# EEM_connector_Wenzel.net
KiCad netlist of a schematic drawn in Altium Designer
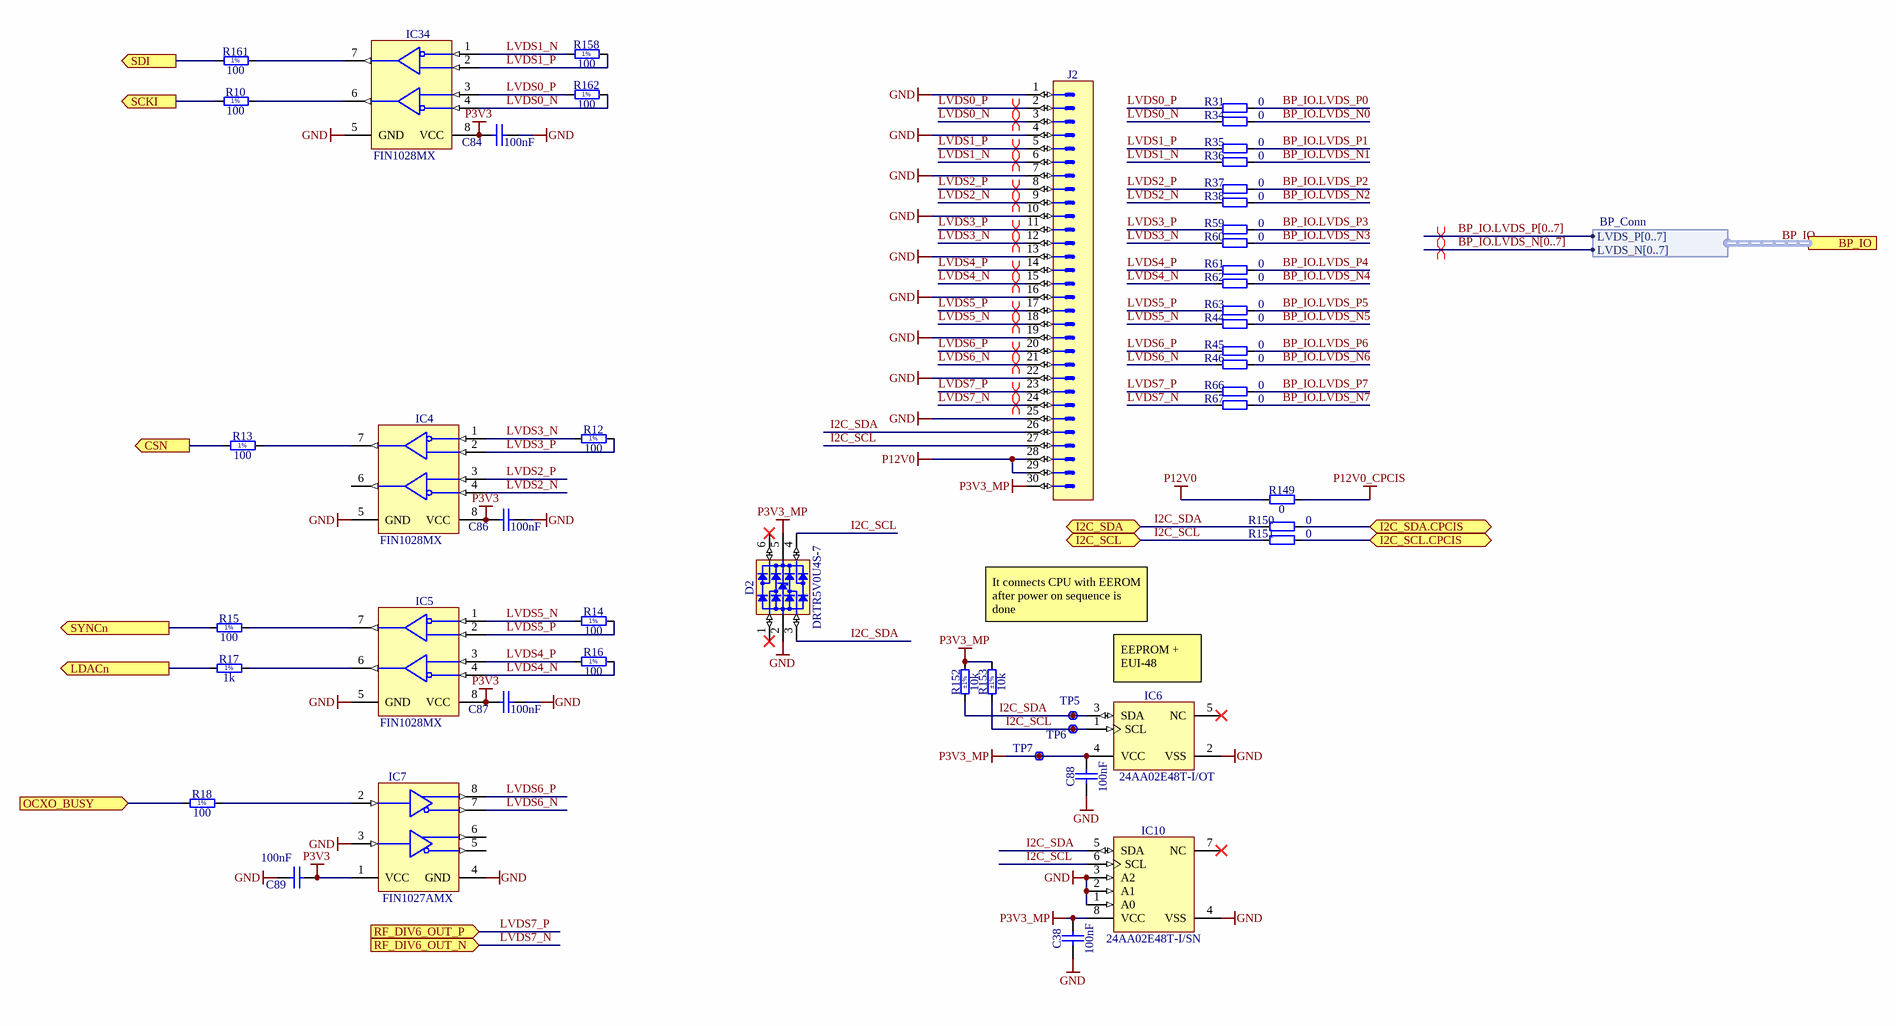
[diagram p0: EEM_connector_Wenzel.SchDoc]

(export (version "E")
  (design (tool "Eeschema 10.0.6"))
  (components
    (comp (ref "C38")
      (value "100nF")
      (footprint "CAPC1005X55N")
      (description "Non-polarised capacitor")
      (fields
        (field (name "PART NUMBER") "CC0402_100NF_16V_10%_X5R")
        (field (name "VOLTAGE") "16V")
        (field (name "AUTHOR") "CERN DEM JLC")
      )
      (libsource (lib "Capacitors") (part "Capacitor - non polarized"))
    )
    (comp (ref "C84")
      (value "100nF")
      (footprint "CAPC1005X55N")
      (description "Non-polarised capacitor")
      (fields
        (field (name "PART NUMBER") "CC0402_100NF_16V_10%_X5R")
        (field (name "VOLTAGE") "16V")
        (field (name "AUTHOR") "CERN DEM JLC")
      )
      (libsource (lib "Capacitors") (part "Capacitor - non polarized"))
    )
    (comp (ref "C86")
      (value "100nF")
      (footprint "CAPC1005X55N")
      (description "Non-polarised capacitor")
      (fields
        (field (name "PART NUMBER") "CC0402_100NF_16V_10%_X5R")
        (field (name "VOLTAGE") "16V")
        (field (name "AUTHOR") "CERN DEM JLC")
      )
      (libsource (lib "Capacitors") (part "Capacitor - non polarized"))
    )
    (comp (ref "C87")
      (value "100nF")
      (footprint "CAPC1005X55N")
      (description "Non-polarised capacitor")
      (fields
        (field (name "PART NUMBER") "CC0402_100NF_16V_10%_X5R")
        (field (name "VOLTAGE") "16V")
        (field (name "AUTHOR") "CERN DEM JLC")
      )
      (libsource (lib "Capacitors") (part "Capacitor - non polarized"))
    )
    (comp (ref "C88")
      (value "100nF")
      (footprint "CAPC1005X55N")
      (description "Non-polarised capacitor")
      (fields
        (field (name "PART NUMBER") "CC0402_100NF_16V_10%_X5R")
        (field (name "VOLTAGE") "16V")
        (field (name "AUTHOR") "CERN DEM JLC")
      )
      (libsource (lib "Capacitors") (part "Capacitor - non polarized"))
    )
    (comp (ref "C89")
      (value "100nF")
      (footprint "CAPC1005X55N")
      (description "Non-polarised capacitor")
      (fields
        (field (name "PART NUMBER") "CC0402_100NF_16V_10%_X5R")
        (field (name "VOLTAGE") "16V")
        (field (name "AUTHOR") "CERN DEM JLC")
      )
      (libsource (lib "Capacitors") (part "Capacitor - non polarized"))
    )
    (comp (ref "D2")
      (value "DRTR5V0U4S-7")
      (footprint "SOT65P210X110-6N")
      (description "Integrated Quad Ultra-Low Capacitance ESD Protection")
      (fields (field (name "MANUFACTURER") "DIODES") (field (name "AUTHOR") "GK"))
      (libsource (lib "Diodes") (part "D_TVS_DRTR5V0U4S-7"))
    )
    (comp (ref "IC4")
      (value "FIN1028MX")
      (footprint "SOIC127P600X175-8N")
      (description "3.3V LVDS 2-Bit High-Speed Differential Reciever")
      (fields (field (name "MANUFACTURER") "ON Semiconductor") (field (name "AUTHOR") "GK"))
      (libsource (lib "LIBRARY_SCH") (part "IFC_FIN1028"))
    )
    (comp (ref "IC5")
      (value "FIN1028MX")
      (footprint "SOIC127P600X175-8N")
      (description "3.3V LVDS 2-Bit High-Speed Differential Reciever")
      (fields (field (name "MANUFACTURER") "ON Semiconductor") (field (name "AUTHOR") "GK"))
      (libsource (lib "LIBRARY_SCH") (part "IFC_FIN1028"))
    )
    (comp (ref "IC6")
      (value "24AA02E48T-I/OT")
      (footprint "SOT95P280X145-5N")
      (description "1.7V-5.5V, 2K I2C Serial EEPROM With EUI-48 Node Identity")
      (fields (field (name "MANUFACTURER") "MICROCHIP TECHNOLOGY") (field (name "AUTHOR") "CERN DEM MR"))
      (libsource (lib "ICs And Semiconductors") (part "24AA02E48T-I/OT"))
    )
    (comp (ref "IC7")
      (value "FIN1027AMX")
      (footprint "SOIC127P600X175-8N")
      (description "3.3V LVDS, 2-Bit, High-Speed, Differential Driver")
      (fields (field (name "MANUFACTURER") "ON Semiconductor") (field (name "AUTHOR") "GK"))
      (libsource (lib "LIBRARY_SCH") (part "IFC_FIN1027A"))
    )
    (comp (ref "IC10")
      (value "24AA02E48T-I/SN")
      (footprint "SOIC127P600X175-8N")
      (description "1.7V-5.5V, 2K I2C™ Serial EEPROMs with EUI-48™ Node Identity")
      (fields (field (name "MANUFACTURER") "MICROCHIP TECHNOLOGY") (field (name "AUTHOR") "CERN DEM MR"))
      (libsource (lib "ICs And Semiconductors") (part "24AA025E48-I/SN"))
    )
    (comp (ref "IC34")
      (value "FIN1028MX")
      (footprint "SOIC127P600X175-8N")
      (description "3.3V LVDS 2-Bit High-Speed Differential Reciever")
      (fields (field (name "MANUFACTURER") "ON Semiconductor") (field (name "AUTHOR") "GK"))
      (libsource (lib "LIBRARY_SCH") (part "IFC_FIN1028"))
    )
    (comp (ref "J2")
      (value "IDC")
      (footprint "3M_N2530-6002RB")
      (description "Connector 30 Male")
      (fields
        (field (name "PART NUMBER") "3M_N2530-6002RB")
        (field (name "MANUFACTURER") "3M")
        (field (name "AUTHOR") "CERN DEM JLC")
      )
      (libsource (lib "Connectors") (part "Connector 30 Male"))
    )
    (comp (ref "R10")
      (value "100")
      (footprint "RESC1005X40N")
      (description "Resistor - 1%")
      (fields
        (field (name "PART NUMBER") "R0402_100R_1%_0.0625W_100PPM")
        (field (name "POWER") "0.0625W")
        (field (name "AUTHOR") "CERN DEM JLC")
      )
      (libsource (lib "Resistors") (part "Resistor - 1%"))
    )
    (comp (ref "R12")
      (value "100")
      (footprint "RESC1005X40N")
      (description "Resistor - 1%")
      (fields
        (field (name "PART NUMBER") "R0402_100R_1%_0.0625W_100PPM")
        (field (name "POWER") "0.0625W")
        (field (name "AUTHOR") "CERN DEM JLC")
      )
      (libsource (lib "Resistors") (part "Resistor - 1%"))
    )
    (comp (ref "R13")
      (value "100")
      (footprint "RESC1005X40N")
      (description "Resistor - 1%")
      (fields
        (field (name "PART NUMBER") "R0402_100R_1%_0.0625W_100PPM")
        (field (name "POWER") "0.0625W")
        (field (name "AUTHOR") "CERN DEM JLC")
      )
      (libsource (lib "Resistors") (part "Resistor - 1%"))
    )
    (comp (ref "R14")
      (value "100")
      (footprint "RESC1005X40N")
      (description "Resistor - 1%")
      (fields
        (field (name "PART NUMBER") "R0402_100R_1%_0.0625W_100PPM")
        (field (name "POWER") "0.0625W")
        (field (name "AUTHOR") "CERN DEM JLC")
      )
      (libsource (lib "Resistors") (part "Resistor - 1%"))
    )
    (comp (ref "R15")
      (value "100")
      (footprint "RESC1005X40N")
      (description "Resistor - 1%")
      (fields
        (field (name "PART NUMBER") "R0402_100R_1%_0.0625W_100PPM")
        (field (name "POWER") "0.0625W")
        (field (name "AUTHOR") "CERN DEM JLC")
      )
      (libsource (lib "Resistors") (part "Resistor - 1%"))
    )
    (comp (ref "R16")
      (value "100")
      (footprint "RESC1005X40N")
      (description "Resistor - 1%")
      (fields
        (field (name "PART NUMBER") "R0402_100R_1%_0.0625W_100PPM")
        (field (name "POWER") "0.0625W")
        (field (name "AUTHOR") "CERN DEM JLC")
      )
      (libsource (lib "Resistors") (part "Resistor - 1%"))
    )
    (comp (ref "R17")
      (value "1k")
      (footprint "RESC1005X40N")
      (description "Resistor - 1%")
      (fields
        (field (name "PART NUMBER") "R0402_1K_1%_0.0625W_100PPM")
        (field (name "POWER") "0.0625W")
        (field (name "AUTHOR") "CERN DEM JLC")
      )
      (libsource (lib "Resistors") (part "Resistor - 1%"))
    )
    (comp (ref "R18")
      (value "100")
      (footprint "RESC1005X40N")
      (description "Resistor - 1%")
      (fields
        (field (name "PART NUMBER") "R0402_100R_1%_0.0625W_100PPM")
        (field (name "POWER") "0.0625W")
        (field (name "AUTHOR") "CERN DEM JLC")
      )
      (libsource (lib "Resistors") (part "Resistor - 1%"))
    )
    (comp (ref "R31")
      (value "0")
      (footprint "RESC1005X40N")
      (description "Resistor")
      (fields
        (field (name "PART NUMBER") "R0402_0R_JUMPER")
        (field (name "MANUFACTURER") "GENERIC")
        (field (name "AUTHOR") "CERN DEM JLC")
      )
      (libsource (lib "Resistors") (part "Resistor"))
    )
    (comp (ref "R34")
      (value "0")
      (footprint "RESC1005X40N")
      (description "Resistor")
      (fields
        (field (name "PART NUMBER") "R0402_0R_JUMPER")
        (field (name "MANUFACTURER") "GENERIC")
        (field (name "AUTHOR") "CERN DEM JLC")
      )
      (libsource (lib "Resistors") (part "Resistor"))
    )
    (comp (ref "R35")
      (value "0")
      (footprint "RESC1005X40N")
      (description "Resistor")
      (fields
        (field (name "PART NUMBER") "R0402_0R_JUMPER")
        (field (name "MANUFACTURER") "GENERIC")
        (field (name "AUTHOR") "CERN DEM JLC")
      )
      (libsource (lib "Resistors") (part "Resistor"))
    )
    (comp (ref "R36")
      (value "0")
      (footprint "RESC1005X40N")
      (description "Resistor")
      (fields
        (field (name "PART NUMBER") "R0402_0R_JUMPER")
        (field (name "MANUFACTURER") "GENERIC")
        (field (name "AUTHOR") "CERN DEM JLC")
      )
      (libsource (lib "Resistors") (part "Resistor"))
    )
    (comp (ref "R37")
      (value "0")
      (footprint "RESC1005X40N")
      (description "Resistor")
      (fields
        (field (name "PART NUMBER") "R0402_0R_JUMPER")
        (field (name "MANUFACTURER") "GENERIC")
        (field (name "AUTHOR") "CERN DEM JLC")
      )
      (libsource (lib "Resistors") (part "Resistor"))
    )
    (comp (ref "R38")
      (value "0")
      (footprint "RESC1005X40N")
      (description "Resistor")
      (fields
        (field (name "PART NUMBER") "R0402_0R_JUMPER")
        (field (name "MANUFACTURER") "GENERIC")
        (field (name "AUTHOR") "CERN DEM JLC")
      )
      (libsource (lib "Resistors") (part "Resistor"))
    )
    (comp (ref "R44")
      (value "0")
      (footprint "RESC1005X40N")
      (description "Resistor")
      (fields
        (field (name "PART NUMBER") "R0402_0R_JUMPER")
        (field (name "MANUFACTURER") "GENERIC")
        (field (name "AUTHOR") "CERN DEM JLC")
      )
      (libsource (lib "Resistors") (part "Resistor"))
    )
    (comp (ref "R45")
      (value "0")
      (footprint "RESC1005X40N")
      (description "Resistor")
      (fields
        (field (name "PART NUMBER") "R0402_0R_JUMPER")
        (field (name "MANUFACTURER") "GENERIC")
        (field (name "AUTHOR") "CERN DEM JLC")
      )
      (libsource (lib "Resistors") (part "Resistor"))
    )
    (comp (ref "R46")
      (value "0")
      (footprint "RESC1005X40N")
      (description "Resistor")
      (fields
        (field (name "PART NUMBER") "R0402_0R_JUMPER")
        (field (name "MANUFACTURER") "GENERIC")
        (field (name "AUTHOR") "CERN DEM JLC")
      )
      (libsource (lib "Resistors") (part "Resistor"))
    )
    (comp (ref "R59")
      (value "0")
      (footprint "RESC1005X40N")
      (description "Resistor")
      (fields
        (field (name "PART NUMBER") "R0402_0R_JUMPER")
        (field (name "MANUFACTURER") "GENERIC")
        (field (name "AUTHOR") "CERN DEM JLC")
      )
      (libsource (lib "Resistors") (part "Resistor"))
    )
    (comp (ref "R60")
      (value "0")
      (footprint "RESC1005X40N")
      (description "Resistor")
      (fields
        (field (name "PART NUMBER") "R0402_0R_JUMPER")
        (field (name "MANUFACTURER") "GENERIC")
        (field (name "AUTHOR") "CERN DEM JLC")
      )
      (libsource (lib "Resistors") (part "Resistor"))
    )
    (comp (ref "R61")
      (value "0")
      (footprint "RESC1005X40N")
      (description "Resistor")
      (fields
        (field (name "PART NUMBER") "R0402_0R_JUMPER")
        (field (name "MANUFACTURER") "GENERIC")
        (field (name "AUTHOR") "CERN DEM JLC")
      )
      (libsource (lib "Resistors") (part "Resistor"))
    )
    (comp (ref "R62")
      (value "0")
      (footprint "RESC1005X40N")
      (description "Resistor")
      (fields
        (field (name "PART NUMBER") "R0402_0R_JUMPER")
        (field (name "MANUFACTURER") "GENERIC")
        (field (name "AUTHOR") "CERN DEM JLC")
      )
      (libsource (lib "Resistors") (part "Resistor"))
    )
    (comp (ref "R63")
      (value "0")
      (footprint "RESC1005X40N")
      (description "Resistor")
      (fields
        (field (name "PART NUMBER") "R0402_0R_JUMPER")
        (field (name "MANUFACTURER") "GENERIC")
        (field (name "AUTHOR") "CERN DEM JLC")
      )
      (libsource (lib "Resistors") (part "Resistor"))
    )
    (comp (ref "R66")
      (value "0")
      (footprint "RESC1005X40N")
      (description "Resistor")
      (fields
        (field (name "PART NUMBER") "R0402_0R_JUMPER")
        (field (name "MANUFACTURER") "GENERIC")
        (field (name "AUTHOR") "CERN DEM JLC")
      )
      (libsource (lib "Resistors") (part "Resistor"))
    )
    (comp (ref "R67")
      (value "0")
      (footprint "RESC1005X40N")
      (description "Resistor")
      (fields
        (field (name "PART NUMBER") "R0402_0R_JUMPER")
        (field (name "MANUFACTURER") "GENERIC")
        (field (name "AUTHOR") "CERN DEM JLC")
      )
      (libsource (lib "Resistors") (part "Resistor"))
    )
    (comp (ref "R149")
      (value "0")
      (footprint "RESC2012X60N")
      (description "Resistor")
      (fields
        (field (name "PART NUMBER") "R0805_0R_JUMPER")
        (field (name "MANUFACTURER") "GENERIC")
        (field (name "AUTHOR") "CERN DEM JLC")
      )
      (libsource (lib "Resistors") (part "Resistor"))
    )
    (comp (ref "R150")
      (value "0")
      (footprint "RESC1005X40N")
      (description "Resistor")
      (fields
        (field (name "PART NUMBER") "R0402_0R_JUMPER")
        (field (name "MANUFACTURER") "GENERIC")
        (field (name "AUTHOR") "CERN DEM JLC")
      )
      (libsource (lib "Resistors") (part "Resistor"))
    )
    (comp (ref "R151")
      (value "0")
      (footprint "RESC1005X40N")
      (description "Resistor")
      (fields
        (field (name "PART NUMBER") "R0402_0R_JUMPER")
        (field (name "MANUFACTURER") "GENERIC")
        (field (name "AUTHOR") "CERN DEM JLC")
      )
      (libsource (lib "Resistors") (part "Resistor"))
    )
    (comp (ref "R152")
      (value "10k")
      (footprint "RESC1005X40N")
      (description "Resistor - 1%")
      (fields
        (field (name "TOLERANCE") "±1%")
        (field (name "PART NUMBER") "R0402_10K_1%_0.0625W_100PPM")
        (field (name "POWER") "0.0625W")
        (field (name "AUTHOR") "CERN DEM JLC")
      )
      (libsource (lib "Resistors") (part "Resistor - 1%"))
    )
    (comp (ref "R153")
      (value "10k")
      (footprint "RESC1005X40N")
      (description "Resistor - 1%")
      (fields
        (field (name "TOLERANCE") "±1%")
        (field (name "PART NUMBER") "R0402_10K_1%_0.0625W_100PPM")
        (field (name "POWER") "0.0625W")
        (field (name "AUTHOR") "CERN DEM JLC")
      )
      (libsource (lib "Resistors") (part "Resistor - 1%"))
    )
    (comp (ref "R158")
      (value "100")
      (footprint "RESC1005X40N")
      (description "Resistor - 1%")
      (fields
        (field (name "PART NUMBER") "R0402_100R_1%_0.0625W_100PPM")
        (field (name "POWER") "0.0625W")
        (field (name "AUTHOR") "CERN DEM JLC")
      )
      (libsource (lib "Resistors") (part "Resistor - 1%"))
    )
    (comp (ref "R161")
      (value "100")
      (footprint "RESC1005X40N")
      (description "Resistor - 1%")
      (fields
        (field (name "PART NUMBER") "R0402_100R_1%_0.0625W_100PPM")
        (field (name "POWER") "0.0625W")
        (field (name "AUTHOR") "CERN DEM JLC")
      )
      (libsource (lib "Resistors") (part "Resistor - 1%"))
    )
    (comp (ref "R162")
      (value "100")
      (footprint "RESC1005X40N")
      (description "Resistor - 1%")
      (fields
        (field (name "PART NUMBER") "R0402_100R_1%_0.0625W_100PPM")
        (field (name "POWER") "0.0625W")
        (field (name "AUTHOR") "CERN DEM JLC")
      )
      (libsource (lib "Resistors") (part "Resistor - 1%"))
    )
    (comp (ref "TP5")
      (value "Test Point")
      (footprint "TPS127")
      (fields (field (name "PART NUMBER") "SMD_PAD_1.27X1.27MM") (field (name "AUTHOR") "CERN DEM JLC"))
      (libsource (lib "Eletro-mechanical") (part "Test Point"))
    )
    (comp (ref "TP6")
      (value "Test Point")
      (footprint "TPS127")
      (fields (field (name "PART NUMBER") "SMD_PAD_1.27X1.27MM") (field (name "AUTHOR") "CERN DEM JLC"))
      (libsource (lib "Eletro-mechanical") (part "Test Point"))
    )
    (comp (ref "TP7")
      (value "Test Point")
      (footprint "TPS127")
      (fields (field (name "PART NUMBER") "SMD_PAD_1.27X1.27MM") (field (name "AUTHOR") "CERN DEM JLC"))
      (libsource (lib "Eletro-mechanical") (part "Test Point"))
    )
  )
  (nets
    (net (code "2") (name "/BP_IO.LVDS_N0") (class "Default")
      (node (ref "R34") (pin "2") (pinfunction "2_2") (pintype "passive"))
    )
    (net (code "3") (name "/BP_IO.LVDS_N1") (class "Default")
      (node (ref "R36") (pin "2") (pinfunction "2_2") (pintype "passive"))
    )
    (net (code "4") (name "/BP_IO.LVDS_N2") (class "Default")
      (node (ref "R38") (pin "2") (pinfunction "2_2") (pintype "passive"))
    )
    (net (code "5") (name "/BP_IO.LVDS_N3") (class "Default")
      (node (ref "R60") (pin "2") (pinfunction "2_2") (pintype "passive"))
    )
    (net (code "6") (name "/BP_IO.LVDS_N4") (class "Default")
      (node (ref "R62") (pin "2") (pinfunction "2_2") (pintype "passive"))
    )
    (net (code "7") (name "/BP_IO.LVDS_N5") (class "Default")
      (node (ref "R44") (pin "2") (pinfunction "2_2") (pintype "passive"))
    )
    (net (code "8") (name "/BP_IO.LVDS_N6") (class "Default")
      (node (ref "R46") (pin "2") (pinfunction "2_2") (pintype "passive"))
    )
    (net (code "9") (name "/BP_IO.LVDS_N7") (class "Default")
      (node (ref "R67") (pin "2") (pinfunction "2_2") (pintype "passive"))
    )
    (net (code "11") (name "/BP_IO.LVDS_P0") (class "Default")
      (node (ref "R31") (pin "2") (pinfunction "2_2") (pintype "passive"))
    )
    (net (code "12") (name "/BP_IO.LVDS_P1") (class "Default")
      (node (ref "R35") (pin "2") (pinfunction "2_2") (pintype "passive"))
    )
    (net (code "13") (name "/BP_IO.LVDS_P2") (class "Default")
      (node (ref "R37") (pin "2") (pinfunction "2_2") (pintype "passive"))
    )
    (net (code "14") (name "/BP_IO.LVDS_P3") (class "Default")
      (node (ref "R59") (pin "2") (pinfunction "2_2") (pintype "passive"))
    )
    (net (code "15") (name "/BP_IO.LVDS_P4") (class "Default")
      (node (ref "R61") (pin "2") (pinfunction "2_2") (pintype "passive"))
    )
    (net (code "16") (name "/BP_IO.LVDS_P5") (class "Default")
      (node (ref "R63") (pin "2") (pinfunction "2_2") (pintype "passive"))
    )
    (net (code "17") (name "/BP_IO.LVDS_P6") (class "Default")
      (node (ref "R45") (pin "2") (pinfunction "2_2") (pintype "passive"))
    )
    (net (code "18") (name "/BP_IO.LVDS_P7") (class "Default")
      (node (ref "R66") (pin "2") (pinfunction "2_2") (pintype "passive"))
    )
    (net (code "21") (name "/CSN") (class "Default")
      (node (ref "R13") (pin "1") (pinfunction "1_1") (pintype "passive"))
    )
    (net (code "22") (name "/I2C_SCL") (class "Default")
      (node (ref "D2") (pin "4") (pinfunction "I/O3_4") (pintype "bidirectional"))
      (node (ref "IC10") (pin "6") (pinfunction "SCL_6") (pintype "input"))
      (node (ref "IC6") (pin "1") (pinfunction "SCL_1") (pintype "input"))
      (node (ref "J2") (pin "27") (pinfunction "27_27") (pintype "bidirectional"))
      (node (ref "R151") (pin "1") (pinfunction "1_1") (pintype "passive"))
      (node (ref "R153") (pin "1") (pinfunction "1_1") (pintype "passive"))
      (node (ref "TP6") (pin "1") (pinfunction "1_1") (pintype "bidirectional"))
    )
    (net (code "23") (name "/I2C_SCL.CPCIS") (class "Default")
      (node (ref "R151") (pin "2") (pinfunction "2_2") (pintype "passive"))
    )
    (net (code "24") (name "/I2C_SDA") (class "Default")
      (node (ref "D2") (pin "3") (pinfunction "I/O2_3") (pintype "bidirectional"))
      (node (ref "IC10") (pin "5") (pinfunction "SDA_5") (pintype "bidirectional"))
      (node (ref "IC6") (pin "3") (pinfunction "SDA_3") (pintype "bidirectional"))
      (node (ref "J2") (pin "26") (pinfunction "26_26") (pintype "bidirectional"))
      (node (ref "R150") (pin "1") (pinfunction "1_1") (pintype "passive"))
      (node (ref "R152") (pin "1") (pinfunction "1_1") (pintype "passive"))
      (node (ref "TP5") (pin "1") (pinfunction "1_1") (pintype "bidirectional"))
    )
    (net (code "25") (name "/I2C_SDA.CPCIS") (class "Default")
      (node (ref "R150") (pin "2") (pinfunction "2_2") (pintype "passive"))
    )
    (net (code "26") (name "/LDACn") (class "Default")
      (node (ref "R17") (pin "1") (pinfunction "1_1") (pintype "passive"))
    )
    (net (code "27") (name "/LVDS0_N") (class "Default")
      (node (ref "IC34") (pin "4") (pinfunction "RIN2-_4") (pintype "input"))
      (node (ref "J2") (pin "3") (pinfunction "3_3") (pintype "bidirectional"))
      (node (ref "R162") (pin "2") (pinfunction "2_2") (pintype "passive"))
      (node (ref "R34") (pin "1") (pinfunction "1_1") (pintype "passive"))
    )
    (net (code "28") (name "/LVDS0_P") (class "Default")
      (node (ref "IC34") (pin "3") (pinfunction "RIN2+_3") (pintype "input"))
      (node (ref "J2") (pin "2") (pinfunction "2_2") (pintype "bidirectional"))
      (node (ref "R162") (pin "1") (pinfunction "1_1") (pintype "passive"))
      (node (ref "R31") (pin "1") (pinfunction "1_1") (pintype "passive"))
    )
    (net (code "29") (name "/LVDS1_N") (class "Default")
      (node (ref "IC34") (pin "1") (pinfunction "RIN1-_1") (pintype "input"))
      (node (ref "J2") (pin "6") (pinfunction "6_6") (pintype "bidirectional"))
      (node (ref "R158") (pin "1") (pinfunction "1_1") (pintype "passive"))
      (node (ref "R36") (pin "1") (pinfunction "1_1") (pintype "passive"))
    )
    (net (code "30") (name "/LVDS1_P") (class "Default")
      (node (ref "IC34") (pin "2") (pinfunction "RIN1+_2") (pintype "input"))
      (node (ref "J2") (pin "5") (pinfunction "5_5") (pintype "bidirectional"))
      (node (ref "R158") (pin "2") (pinfunction "2_2") (pintype "passive"))
      (node (ref "R35") (pin "1") (pinfunction "1_1") (pintype "passive"))
    )
    (net (code "31") (name "/LVDS2_N") (class "Default")
      (node (ref "IC4") (pin "4") (pinfunction "RIN2-_4") (pintype "input"))
      (node (ref "J2") (pin "9") (pinfunction "9_9") (pintype "bidirectional"))
      (node (ref "R38") (pin "1") (pinfunction "1_1") (pintype "passive"))
    )
    (net (code "32") (name "/LVDS2_P") (class "Default")
      (node (ref "IC4") (pin "3") (pinfunction "RIN2+_3") (pintype "input"))
      (node (ref "J2") (pin "8") (pinfunction "8_8") (pintype "bidirectional"))
      (node (ref "R37") (pin "1") (pinfunction "1_1") (pintype "passive"))
    )
    (net (code "33") (name "/LVDS3_N") (class "Default")
      (node (ref "IC4") (pin "1") (pinfunction "RIN1-_1") (pintype "input"))
      (node (ref "J2") (pin "12") (pinfunction "12_12") (pintype "bidirectional"))
      (node (ref "R12") (pin "1") (pinfunction "1_1") (pintype "passive"))
      (node (ref "R60") (pin "1") (pinfunction "1_1") (pintype "passive"))
    )
    (net (code "34") (name "/LVDS3_P") (class "Default")
      (node (ref "IC4") (pin "2") (pinfunction "RIN1+_2") (pintype "input"))
      (node (ref "J2") (pin "11") (pinfunction "11_11") (pintype "bidirectional"))
      (node (ref "R12") (pin "2") (pinfunction "2_2") (pintype "passive"))
      (node (ref "R59") (pin "1") (pinfunction "1_1") (pintype "passive"))
    )
    (net (code "35") (name "/LVDS4_N") (class "Default")
      (node (ref "IC5") (pin "4") (pinfunction "RIN2-_4") (pintype "input"))
      (node (ref "J2") (pin "15") (pinfunction "15_15") (pintype "bidirectional"))
      (node (ref "R16") (pin "2") (pinfunction "2_2") (pintype "passive"))
      (node (ref "R62") (pin "1") (pinfunction "1_1") (pintype "passive"))
    )
    (net (code "36") (name "/LVDS4_P") (class "Default")
      (node (ref "IC5") (pin "3") (pinfunction "RIN2+_3") (pintype "input"))
      (node (ref "J2") (pin "14") (pinfunction "14_14") (pintype "bidirectional"))
      (node (ref "R16") (pin "1") (pinfunction "1_1") (pintype "passive"))
      (node (ref "R61") (pin "1") (pinfunction "1_1") (pintype "passive"))
    )
    (net (code "37") (name "/LVDS5_N") (class "Default")
      (node (ref "IC5") (pin "1") (pinfunction "RIN1-_1") (pintype "input"))
      (node (ref "J2") (pin "18") (pinfunction "18_18") (pintype "bidirectional"))
      (node (ref "R14") (pin "1") (pinfunction "1_1") (pintype "passive"))
      (node (ref "R44") (pin "1") (pinfunction "1_1") (pintype "passive"))
    )
    (net (code "38") (name "/LVDS5_P") (class "Default")
      (node (ref "IC5") (pin "2") (pinfunction "RIN1+_2") (pintype "input"))
      (node (ref "J2") (pin "17") (pinfunction "17_17") (pintype "bidirectional"))
      (node (ref "R14") (pin "2") (pinfunction "2_2") (pintype "passive"))
      (node (ref "R63") (pin "1") (pinfunction "1_1") (pintype "passive"))
    )
    (net (code "39") (name "/LVDS6_N") (class "Default")
      (node (ref "IC7") (pin "7") (pinfunction "DOUT-_7") (pintype "output"))
      (node (ref "J2") (pin "21") (pinfunction "21_21") (pintype "bidirectional"))
      (node (ref "R46") (pin "1") (pinfunction "1_1") (pintype "passive"))
    )
    (net (code "40") (name "/LVDS6_P") (class "Default")
      (node (ref "IC7") (pin "8") (pinfunction "DOUT+_8") (pintype "output"))
      (node (ref "J2") (pin "20") (pinfunction "20_20") (pintype "bidirectional"))
      (node (ref "R45") (pin "1") (pinfunction "1_1") (pintype "passive"))
    )
    (net (code "41") (name "/LVDS7_N") (class "Default")
      (node (ref "J2") (pin "24") (pinfunction "24_24") (pintype "bidirectional"))
      (node (ref "R67") (pin "1") (pinfunction "1_1") (pintype "passive"))
    )
    (net (code "42") (name "/LVDS7_P") (class "Default")
      (node (ref "J2") (pin "23") (pinfunction "23_23") (pintype "bidirectional"))
      (node (ref "R66") (pin "1") (pinfunction "1_1") (pintype "passive"))
    )
    (net (code "43") (name "/OCXO_BUSY") (class "Default")
      (node (ref "R18") (pin "1") (pinfunction "1_1") (pintype "passive"))
    )
    (net (code "44") (name "/SCKI") (class "Default")
      (node (ref "R10") (pin "1") (pinfunction "1_1") (pintype "passive"))
    )
    (net (code "45") (name "/SDI") (class "Default")
      (node (ref "R161") (pin "1") (pinfunction "1_1") (pintype "passive"))
    )
    (net (code "46") (name "/SYNCn") (class "Default")
      (node (ref "R15") (pin "1") (pinfunction "1_1") (pintype "passive"))
    )
    (net (code "47") (name "GND") (class "Default")
      (node (ref "C38") (pin "1") (pinfunction "1_1") (pintype "passive"))
      (node (ref "C84") (pin "1") (pinfunction "1_1") (pintype "passive"))
      (node (ref "C86") (pin "1") (pinfunction "1_1") (pintype "passive"))
      (node (ref "C87") (pin "1") (pinfunction "1_1") (pintype "passive"))
      (node (ref "C88") (pin "1") (pinfunction "1_1") (pintype "passive"))
      (node (ref "C89") (pin "1") (pinfunction "1_1") (pintype "passive"))
      (node (ref "D2") (pin "2") (pinfunction "GND_2") (pintype "power_in"))
      (node (ref "IC10") (pin "1") (pinfunction "A0_1") (pintype "input"))
      (node (ref "IC10") (pin "2") (pinfunction "A1_2") (pintype "input"))
      (node (ref "IC10") (pin "3") (pinfunction "A2_3") (pintype "input"))
      (node (ref "IC10") (pin "4") (pinfunction "VSS_4") (pintype "power_in"))
      (node (ref "IC34") (pin "5") (pinfunction "GND_5") (pintype "power_in"))
      (node (ref "IC4") (pin "5") (pinfunction "GND_5") (pintype "power_in"))
      (node (ref "IC5") (pin "5") (pinfunction "GND_5") (pintype "power_in"))
      (node (ref "IC6") (pin "2") (pinfunction "VSS_2") (pintype "power_in"))
      (node (ref "IC7") (pin "3") (pinfunction "DIN2RIN-_3") (pintype "input"))
      (node (ref "IC7") (pin "4") (pinfunction "GND_4") (pintype "power_in"))
      (node (ref "J2") (pin "1") (pinfunction "1_1") (pintype "bidirectional"))
      (node (ref "J2") (pin "10") (pinfunction "10_10") (pintype "bidirectional"))
      (node (ref "J2") (pin "13") (pinfunction "13_13") (pintype "bidirectional"))
      (node (ref "J2") (pin "16") (pinfunction "16_16") (pintype "bidirectional"))
      (node (ref "J2") (pin "19") (pinfunction "19_19") (pintype "bidirectional"))
      (node (ref "J2") (pin "22") (pinfunction "22_22") (pintype "bidirectional"))
      (node (ref "J2") (pin "25") (pinfunction "25_25") (pintype "bidirectional"))
      (node (ref "J2") (pin "4") (pinfunction "4_4") (pintype "bidirectional"))
      (node (ref "J2") (pin "7") (pinfunction "7_7") (pintype "bidirectional"))
    )
    (net (code "48") (name "Net-(IC4-ROUT1)") (class "Default")
      (node (ref "IC4") (pin "7") (pinfunction "ROUT1_7") (pintype "output"))
      (node (ref "R13") (pin "2") (pinfunction "2_2") (pintype "passive"))
    )
    (net (code "49") (name "Net-(IC5-ROUT1)") (class "Default")
      (node (ref "IC5") (pin "7") (pinfunction "ROUT1_7") (pintype "output"))
      (node (ref "R15") (pin "2") (pinfunction "2_2") (pintype "passive"))
    )
    (net (code "50") (name "Net-(IC5-ROUT2)") (class "Default")
      (node (ref "IC5") (pin "6") (pinfunction "ROUT2_6") (pintype "output"))
      (node (ref "R17") (pin "2") (pinfunction "2_2") (pintype "passive"))
    )
    (net (code "51") (name "Net-(IC7-DIN1)") (class "Default")
      (node (ref "IC7") (pin "2") (pinfunction "DIN1_2") (pintype "input"))
      (node (ref "R18") (pin "2") (pinfunction "2_2") (pintype "passive"))
    )
    (net (code "52") (name "Net-(IC34-ROUT1)") (class "Default")
      (node (ref "IC34") (pin "7") (pinfunction "ROUT1_7") (pintype "output"))
      (node (ref "R161") (pin "2") (pinfunction "2_2") (pintype "passive"))
    )
    (net (code "53") (name "Net-(IC34-ROUT2)") (class "Default")
      (node (ref "IC34") (pin "6") (pinfunction "ROUT2_6") (pintype "output"))
      (node (ref "R10") (pin "2") (pinfunction "2_2") (pintype "passive"))
    )
    (net (code "54") (name "P3V3") (class "Default")
      (node (ref "C84") (pin "2") (pinfunction "2_2") (pintype "passive"))
      (node (ref "C86") (pin "2") (pinfunction "2_2") (pintype "passive"))
      (node (ref "C87") (pin "2") (pinfunction "2_2") (pintype "passive"))
      (node (ref "C89") (pin "2") (pinfunction "2_2") (pintype "passive"))
      (node (ref "IC34") (pin "8") (pinfunction "VCC_8") (pintype "power_in"))
      (node (ref "IC4") (pin "8") (pinfunction "VCC_8") (pintype "power_in"))
      (node (ref "IC5") (pin "8") (pinfunction "VCC_8") (pintype "power_in"))
      (node (ref "IC7") (pin "1") (pinfunction "VCC_1") (pintype "power_in"))
    )
    (net (code "55") (name "P3V3_MP") (class "Default")
      (node (ref "C38") (pin "2") (pinfunction "2_2") (pintype "passive"))
      (node (ref "C88") (pin "2") (pinfunction "2_2") (pintype "passive"))
      (node (ref "D2") (pin "5") (pinfunction "VBUS_5") (pintype "power_in"))
      (node (ref "IC10") (pin "8") (pinfunction "VCC_8") (pintype "power_in"))
      (node (ref "IC6") (pin "4") (pinfunction "VCC_4") (pintype "power_in"))
      (node (ref "J2") (pin "30") (pinfunction "30_30") (pintype "bidirectional"))
      (node (ref "R152") (pin "2") (pinfunction "2_2") (pintype "passive"))
      (node (ref "R153") (pin "2") (pinfunction "2_2") (pintype "passive"))
      (node (ref "TP7") (pin "1") (pinfunction "1_1") (pintype "bidirectional"))
    )
    (net (code "56") (name "P12V0") (class "Default")
      (node (ref "J2") (pin "28") (pinfunction "28_28") (pintype "bidirectional"))
      (node (ref "J2") (pin "29") (pinfunction "29_29") (pintype "bidirectional"))
      (node (ref "R149") (pin "1") (pinfunction "1_1") (pintype "passive"))
    )
    (net (code "57") (name "P12V0_CPCIS") (class "Default")
      (node (ref "R149") (pin "2") (pinfunction "2_2") (pintype "passive"))
    )
    (net (code "58") (name "unconnected-(D2-I{slash}O1-Pad1)") (class "Default")
      (node (ref "D2") (pin "1") (pinfunction "I/O1_1") (pintype "bidirectional+no_connect"))
    )
    (net (code "59") (name "unconnected-(D2-I{slash}O4-Pad6)") (class "Default")
      (node (ref "D2") (pin "6") (pinfunction "I/O4_6") (pintype "bidirectional+no_connect"))
    )
    (net (code "60") (name "unconnected-(IC4-ROUT2-Pad6)") (class "Default")
      (node (ref "IC4") (pin "6") (pinfunction "ROUT2_6") (pintype "output"))
    )
    (net (code "61") (name "unconnected-(IC6-NC-Pad5)") (class "Default")
      (node (ref "IC6") (pin "5") (pinfunction "NC_5") (pintype "passive+no_connect"))
    )
    (net (code "62") (name "unconnected-(IC7-DOUT+-Pad6)") (class "Default")
      (node (ref "IC7") (pin "6") (pinfunction "DOUT+_6") (pintype "output"))
    )
    (net (code "63") (name "unconnected-(IC7-DOUT--Pad5)") (class "Default")
      (node (ref "IC7") (pin "5") (pinfunction "DOUT-_5") (pintype "output"))
    )
    (net (code "64") (name "unconnected-(IC10-NC-Pad7)") (class "Default")
      (node (ref "IC10") (pin "7") (pinfunction "NC_7") (pintype "passive+no_connect"))
    )
  )
)
